# eva01_connectors.net
KiCad netlist of a schematic drawn in Altium Designer
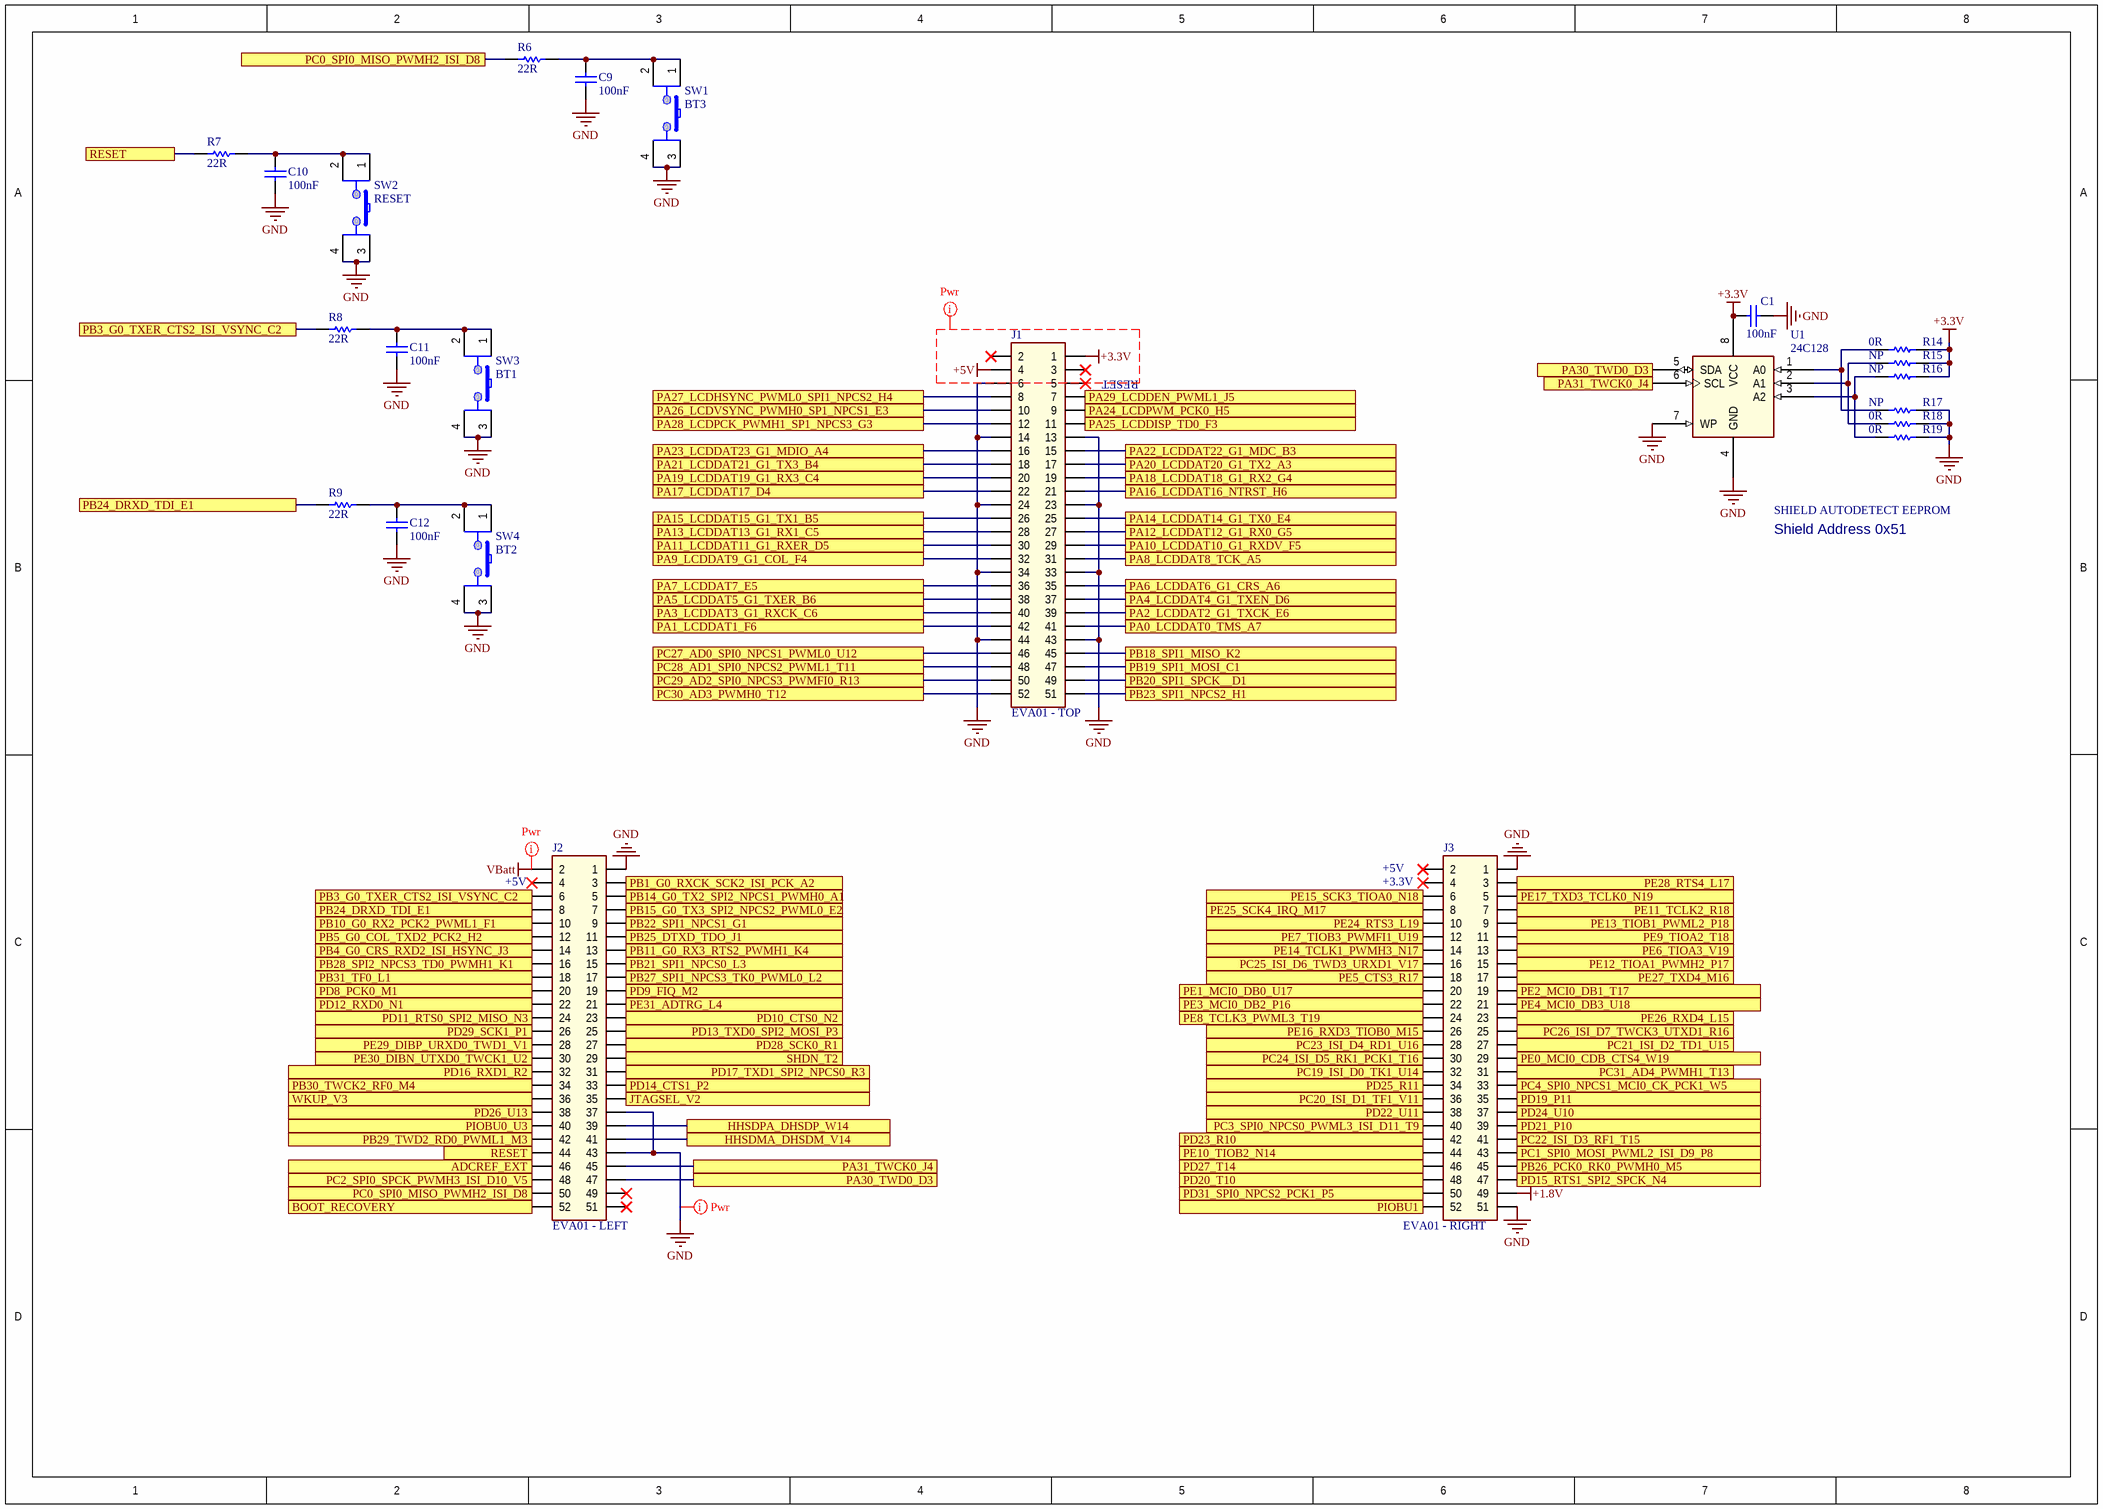
[diagram p0: eva01_connectors.SchDoc]

(export (version "E")
  (design (tool "Eeschema 10.0.6"))
  (components
    (comp (ref "C1")
      (value "100nF")
      (footprint "0603_[1608]")
      (description "Ceramic X7R 50V")
      (fields (field (name "PUBLISHER") "Altium Limited"))
      (libsource (lib "DEVELER_Library") (part "Cap"))
    )
    (comp (ref "C9")
      (value "100nF")
      (footprint "0603_[1608]")
      (description "Ceramic X7R 50V")
      (fields (field (name "PUBLISHER") "Altium Limited"))
      (libsource (lib "DEVELER_Library") (part "Cap"))
    )
    (comp (ref "C10")
      (value "100nF")
      (footprint "0603_[1608]")
      (description "Ceramic X7R 50V")
      (fields (field (name "PUBLISHER") "Altium Limited"))
      (libsource (lib "DEVELER_Library") (part "Cap"))
    )
    (comp (ref "C11")
      (value "100nF")
      (footprint "0603_[1608]")
      (description "Ceramic X7R 50V")
      (fields (field (name "PUBLISHER") "Altium Limited"))
      (libsource (lib "DEVELER_Library") (part "Cap"))
    )
    (comp (ref "C12")
      (value "100nF")
      (footprint "0603_[1608]")
      (description "Ceramic X7R 50V")
      (fields (field (name "PUBLISHER") "Altium Limited"))
      (libsource (lib "DEVELER_Library") (part "Cap"))
    )
    (comp (ref "J1")
      (value "EVA01 - TOP")
      (footprint "SOCKET_2x26_2.54MM_THD")
      (description "Socket Header, 52 pin, 26x2, 2.54mm, H=8.5mm")
      (fields (field (name "PART NUMBER") "Tyco 1-1634688"))
      (libsource (lib "DEVELER_Library") (part "Header 26x2"))
    )
    (comp (ref "J2")
      (value "EVA01 - LEFT")
      (footprint "SOCKET_2x26_2.54MM_THD")
      (description "Socket Header, 52 pin, 26x2, 2.54mm, H=8.5mm")
      (fields (field (name "PART NUMBER") "Tyco 1-1634688"))
      (libsource (lib "DEVELER_Library") (part "Header 26x2"))
    )
    (comp (ref "J3")
      (value "EVA01 - RIGHT")
      (footprint "SOCKET_2x26_2.54MM_THD")
      (description "Socket Header, 52 pin, 26x2, 2.54mm, H=8.5mm")
      (fields (field (name "PART NUMBER") "Tyco 1-1634688"))
      (libsource (lib "DEVELER_Library") (part "Header 26x2"))
    )
    (comp (ref "R6")
      (value "22R")
      (footprint "0603_[1608]")
      (description "Resistor")
      (fields (field (name "PUBLISHER") "Altium Limited"))
      (libsource (lib "DEVELER_Library") (part "Res1"))
    )
    (comp (ref "R7")
      (value "22R")
      (footprint "0603_[1608]")
      (description "Resistor")
      (fields (field (name "PUBLISHER") "Altium Limited"))
      (libsource (lib "DEVELER_Library") (part "Res1"))
    )
    (comp (ref "R8")
      (value "22R")
      (footprint "0603_[1608]")
      (description "Resistor")
      (fields (field (name "PUBLISHER") "Altium Limited"))
      (libsource (lib "DEVELER_Library") (part "Res1"))
    )
    (comp (ref "R9")
      (value "22R")
      (footprint "0603_[1608]")
      (description "Resistor")
      (fields (field (name "PUBLISHER") "Altium Limited"))
      (libsource (lib "DEVELER_Library") (part "Res1"))
    )
    (comp (ref "R14")
      (value "0R")
      (footprint "0603_[1608]")
      (description "Resistor")
      (fields (field (name "PUBLISHER") "Altium Limited"))
      (libsource (lib "project42_lib") (part "Res1"))
    )
    (comp (ref "R15")
      (value "NP")
      (footprint "0603_[1608]")
      (description "Resistor")
      (fields (field (name "PUBLISHER") "Altium Limited"))
      (libsource (lib "project42_lib") (part "Res1"))
    )
    (comp (ref "R16")
      (value "NP")
      (footprint "0603_[1608]")
      (description "Resistor")
      (fields (field (name "PUBLISHER") "Altium Limited"))
      (libsource (lib "project42_lib") (part "Res1"))
    )
    (comp (ref "R17")
      (value "NP")
      (footprint "0603_[1608]")
      (description "Resistor")
      (fields (field (name "PUBLISHER") "Altium Limited"))
      (libsource (lib "project42_lib") (part "Res1"))
    )
    (comp (ref "R18")
      (value "0R")
      (footprint "0603_[1608]")
      (description "Resistor")
      (fields (field (name "PUBLISHER") "Altium Limited"))
      (libsource (lib "project42_lib") (part "Res1"))
    )
    (comp (ref "R19")
      (value "0R")
      (footprint "0603_[1608]")
      (description "Resistor")
      (fields (field (name "PUBLISHER") "Altium Limited"))
      (libsource (lib "project42_lib") (part "Res1"))
    )
    (comp (ref "SW1")
      (value "BT3")
      (footprint "TACTILE_SWITCH_6x6MM_SMD")
      (description "Tactile switch smd H=4.3mm 10x6mm (like cod. Farnell 2435308)")
      (libsource (lib "DEVELER_Library") (part "tactile_switch"))
    )
    (comp (ref "SW2")
      (value "RESET")
      (footprint "TACTILE_SWITCH_6x6MM_SMD")
      (description "Tactile switch smd H=4.3mm 10x6mm (like cod. Farnell 2435308)")
      (libsource (lib "DEVELER_Library") (part "tactile_switch"))
    )
    (comp (ref "SW3")
      (value "BT1")
      (footprint "TACTILE_SWITCH_6x6MM_SMD")
      (description "Tactile switch smd H=4.3mm 10x6mm (like cod. Farnell 2435308)")
      (libsource (lib "DEVELER_Library") (part "tactile_switch"))
    )
    (comp (ref "SW4")
      (value "BT2")
      (footprint "TACTILE_SWITCH_6x6MM_SMD")
      (description "Tactile switch smd H=4.3mm 10x6mm (like cod. Farnell 2435308)")
      (libsource (lib "DEVELER_Library") (part "tactile_switch"))
    )
    (comp (ref "U1")
      (value "24C128")
      (footprint "SOIC8")
      (description "EEPROM")
      (libsource (lib "DEVELER_Library") (part "EEPROM-SOIC8"))
    )
  )
  (nets
    (net (code "1") (name "+1.8V") (class "Default")
      (node (ref "J3") (pin "49") (pinfunction "49_49") (pintype "passive"))
    )
    (net (code "2") (name "+3.3V") (class "Default")
      (node (ref "C1") (pin "2") (pinfunction "2_2") (pintype "passive"))
      (node (ref "J1") (pin "1") (pinfunction "1_1") (pintype "passive"))
      (node (ref "R14") (pin "1") (pinfunction "1_1") (pintype "passive"))
      (node (ref "R15") (pin "1") (pinfunction "1_1") (pintype "passive"))
      (node (ref "R16") (pin "1") (pinfunction "1_1") (pintype "passive"))
      (node (ref "U1") (pin "8") (pinfunction "VCC_8") (pintype "power_in"))
    )
    (net (code "3") (name "+5V") (class "Default")
      (node (ref "J1") (pin "4") (pinfunction "4_4") (pintype "passive"))
    )
    (net (code "4") (name "/ADCREF_EXT") (class "Default")
      (node (ref "J2") (pin "46") (pinfunction "46_46") (pintype "passive"))
    )
    (net (code "5") (name "/BOOT_RECOVERY") (class "Default")
      (node (ref "J2") (pin "52") (pinfunction "52_52") (pintype "passive"))
    )
    (net (code "6") (name "/HHSDMA_DHSDM_V14") (class "Default")
      (node (ref "J2") (pin "41") (pinfunction "41_41") (pintype "passive"))
    )
    (net (code "7") (name "/HHSDPA_DHSDP_W14") (class "Default")
      (node (ref "J2") (pin "39") (pinfunction "39_39") (pintype "passive"))
    )
    (net (code "8") (name "/JTAGSEL_V2") (class "Default")
      (node (ref "J2") (pin "35") (pinfunction "35_35") (pintype "passive"))
    )
    (net (code "9") (name "/PA0_LCDDAT0_TMS_A7") (class "Default")
      (node (ref "J1") (pin "41") (pinfunction "41_41") (pintype "passive"))
    )
    (net (code "10") (name "/PA1_LCDDAT1_F6") (class "Default")
      (node (ref "J1") (pin "42") (pinfunction "42_42") (pintype "passive"))
    )
    (net (code "11") (name "/PA2_LCDDAT2_G1_TXCK_E6") (class "Default")
      (node (ref "J1") (pin "39") (pinfunction "39_39") (pintype "passive"))
    )
    (net (code "12") (name "/PA3_LCDDAT3_G1_RXCK_C6") (class "Default")
      (node (ref "J1") (pin "40") (pinfunction "40_40") (pintype "passive"))
    )
    (net (code "13") (name "/PA4_LCDDAT4_G1_TXEN_D6") (class "Default")
      (node (ref "J1") (pin "37") (pinfunction "37_37") (pintype "passive"))
    )
    (net (code "14") (name "/PA5_LCDDAT5_G1_TXER_B6") (class "Default")
      (node (ref "J1") (pin "38") (pinfunction "38_38") (pintype "passive"))
    )
    (net (code "15") (name "/PA6_LCDDAT6_G1_CRS_A6") (class "Default")
      (node (ref "J1") (pin "35") (pinfunction "35_35") (pintype "passive"))
    )
    (net (code "16") (name "/PA7_LCDDAT7_E5") (class "Default")
      (node (ref "J1") (pin "36") (pinfunction "36_36") (pintype "passive"))
    )
    (net (code "17") (name "/PA8_LCDDAT8_TCK_A5") (class "Default")
      (node (ref "J1") (pin "31") (pinfunction "31_31") (pintype "passive"))
    )
    (net (code "18") (name "/PA9_LCDDAT9_G1_COL_F4") (class "Default")
      (node (ref "J1") (pin "32") (pinfunction "32_32") (pintype "passive"))
    )
    (net (code "19") (name "/PA10_LCDDAT10_G1_RXDV_F5") (class "Default")
      (node (ref "J1") (pin "29") (pinfunction "29_29") (pintype "passive"))
    )
    (net (code "20") (name "/PA11_LCDDAT11_G1_RXER_D5") (class "Default")
      (node (ref "J1") (pin "30") (pinfunction "30_30") (pintype "passive"))
    )
    (net (code "21") (name "/PA12_LCDDAT12_G1_RX0_G5") (class "Default")
      (node (ref "J1") (pin "27") (pinfunction "27_27") (pintype "passive"))
    )
    (net (code "22") (name "/PA13_LCDDAT13_G1_RX1_C5") (class "Default")
      (node (ref "J1") (pin "28") (pinfunction "28_28") (pintype "passive"))
    )
    (net (code "23") (name "/PA14_LCDDAT14_G1_TX0_E4") (class "Default")
      (node (ref "J1") (pin "25") (pinfunction "25_25") (pintype "passive"))
    )
    (net (code "24") (name "/PA15_LCDDAT15_G1_TX1_B5") (class "Default")
      (node (ref "J1") (pin "26") (pinfunction "26_26") (pintype "passive"))
    )
    (net (code "25") (name "/PA16_LCDDAT16_NTRST_H6") (class "Default")
      (node (ref "J1") (pin "21") (pinfunction "21_21") (pintype "passive"))
    )
    (net (code "26") (name "/PA17_LCDDAT17_D4") (class "Default")
      (node (ref "J1") (pin "22") (pinfunction "22_22") (pintype "passive"))
    )
    (net (code "27") (name "/PA18_LCDDAT18_G1_RX2_G4") (class "Default")
      (node (ref "J1") (pin "19") (pinfunction "19_19") (pintype "passive"))
    )
    (net (code "28") (name "/PA19_LCDDAT19_G1_RX3_C4") (class "Default")
      (node (ref "J1") (pin "20") (pinfunction "20_20") (pintype "passive"))
    )
    (net (code "29") (name "/PA20_LCDDAT20_G1_TX2_A3") (class "Default")
      (node (ref "J1") (pin "17") (pinfunction "17_17") (pintype "passive"))
    )
    (net (code "30") (name "/PA21_LCDDAT21_G1_TX3_B4") (class "Default")
      (node (ref "J1") (pin "18") (pinfunction "18_18") (pintype "passive"))
    )
    (net (code "31") (name "/PA22_LCDDAT22_G1_MDC_B3") (class "Default")
      (node (ref "J1") (pin "15") (pinfunction "15_15") (pintype "passive"))
    )
    (net (code "32") (name "/PA23_LCDDAT23_G1_MDIO_A4") (class "Default")
      (node (ref "J1") (pin "16") (pinfunction "16_16") (pintype "passive"))
    )
    (net (code "33") (name "/PA24_LCDPWM_PCK0_H5") (class "Default")
      (node (ref "J1") (pin "9") (pinfunction "9_9") (pintype "passive"))
    )
    (net (code "34") (name "/PA25_LCDDISP_TD0_F3") (class "Default")
      (node (ref "J1") (pin "11") (pinfunction "11_11") (pintype "passive"))
    )
    (net (code "35") (name "/PA26_LCDVSYNC_PWMH0_SP1_NPCS1_E3") (class "Default")
      (node (ref "J1") (pin "10") (pinfunction "10_10") (pintype "passive"))
    )
    (net (code "36") (name "/PA27_LCDHSYNC_PWML0_SPI1_NPCS2_H4") (class "Default")
      (node (ref "J1") (pin "8") (pinfunction "8_8") (pintype "passive"))
    )
    (net (code "37") (name "/PA28_LCDPCK_PWMH1_SP1_NPCS3_G3") (class "Default")
      (node (ref "J1") (pin "12") (pinfunction "12_12") (pintype "passive"))
    )
    (net (code "38") (name "/PA29_LCDDEN_PWML1_J5") (class "Default")
      (node (ref "J1") (pin "7") (pinfunction "7_7") (pintype "passive"))
    )
    (net (code "39") (name "/PA30_TWD0_D3") (class "Default")
      (node (ref "J2") (pin "47") (pinfunction "47_47") (pintype "passive"))
      (node (ref "U1") (pin "5") (pinfunction "SDA_5") (pintype "bidirectional"))
    )
    (net (code "40") (name "/PA31_TWCK0_J4") (class "Default")
      (node (ref "J2") (pin "45") (pinfunction "45_45") (pintype "passive"))
      (node (ref "U1") (pin "6") (pinfunction "SCL_6") (pintype "input"))
    )
    (net (code "41") (name "/PB1_G0_RXCK_SCK2_ISI_PCK_A2") (class "Default")
      (node (ref "J2") (pin "3") (pinfunction "3_3") (pintype "passive"))
    )
    (net (code "42") (name "/PB3_G0_TXER_CTS2_ISI_VSYNC_C2") (class "Default")
      (node (ref "J2") (pin "6") (pinfunction "6_6") (pintype "passive"))
      (node (ref "R8") (pin "2") (pinfunction "2_2") (pintype "passive"))
    )
    (net (code "43") (name "/PB4_G0_CRS_RXD2_ISI_HSYNC_J3") (class "Default")
      (node (ref "J2") (pin "14") (pinfunction "14_14") (pintype "passive"))
    )
    (net (code "44") (name "/PB5_G0_COL_TXD2_PCK2_H2") (class "Default")
      (node (ref "J2") (pin "12") (pinfunction "12_12") (pintype "passive"))
    )
    (net (code "45") (name "/PB10_G0_RX2_PCK2_PWML1_F1") (class "Default")
      (node (ref "J2") (pin "10") (pinfunction "10_10") (pintype "passive"))
    )
    (net (code "46") (name "/PB11_G0_RX3_RTS2_PWMH1_K4") (class "Default")
      (node (ref "J2") (pin "13") (pinfunction "13_13") (pintype "passive"))
    )
    (net (code "47") (name "/PB14_G0_TX2_SPI2_NPCS1_PWMH0_A1") (class "Default")
      (node (ref "J2") (pin "5") (pinfunction "5_5") (pintype "passive"))
    )
    (net (code "48") (name "/PB15_G0_TX3_SPI2_NPCS2_PWML0_E2") (class "Default")
      (node (ref "J2") (pin "7") (pinfunction "7_7") (pintype "passive"))
    )
    (net (code "49") (name "/PB18_SPI1_MISO_K2") (class "Default")
      (node (ref "J1") (pin "45") (pinfunction "45_45") (pintype "passive"))
    )
    (net (code "50") (name "/PB19_SPI1_MOSI_C1") (class "Default")
      (node (ref "J1") (pin "47") (pinfunction "47_47") (pintype "passive"))
    )
    (net (code "51") (name "/PB20_SPI1_SPCK__D1") (class "Default")
      (node (ref "J1") (pin "49") (pinfunction "49_49") (pintype "passive"))
    )
    (net (code "52") (name "/PB21_SPI1_NPCS0_L3") (class "Default")
      (node (ref "J2") (pin "15") (pinfunction "15_15") (pintype "passive"))
    )
    (net (code "53") (name "/PB22_SPI1_NPCS1_G1") (class "Default")
      (node (ref "J2") (pin "9") (pinfunction "9_9") (pintype "passive"))
    )
    (net (code "54") (name "/PB23_SPI1_NPCS2_H1") (class "Default")
      (node (ref "J1") (pin "51") (pinfunction "51_51") (pintype "passive"))
    )
    (net (code "55") (name "/PB24_DRXD_TDI_E1") (class "Default")
      (node (ref "J2") (pin "8") (pinfunction "8_8") (pintype "passive"))
      (node (ref "R9") (pin "2") (pinfunction "2_2") (pintype "passive"))
    )
    (net (code "56") (name "/PB25_DTXD_TDO_J1") (class "Default")
      (node (ref "J2") (pin "11") (pinfunction "11_11") (pintype "passive"))
    )
    (net (code "57") (name "/PB26_PCK0_RK0_PWMH0_M5") (class "Default")
      (node (ref "J3") (pin "45") (pinfunction "45_45") (pintype "passive"))
    )
    (net (code "58") (name "/PB27_SPI1_NPCS3_TK0_PWML0_L2") (class "Default")
      (node (ref "J2") (pin "17") (pinfunction "17_17") (pintype "passive"))
    )
    (net (code "59") (name "/PB28_SPI2_NPCS3_TD0_PWMH1_K1") (class "Default")
      (node (ref "J2") (pin "16") (pinfunction "16_16") (pintype "passive"))
    )
    (net (code "60") (name "/PB29_TWD2_RD0_PWML1_M3") (class "Default")
      (node (ref "J2") (pin "42") (pinfunction "42_42") (pintype "passive"))
    )
    (net (code "61") (name "/PB30_TWCK2_RF0_M4") (class "Default")
      (node (ref "J2") (pin "34") (pinfunction "34_34") (pintype "passive"))
    )
    (net (code "62") (name "/PB31_TF0_L1") (class "Default")
      (node (ref "J2") (pin "18") (pinfunction "18_18") (pintype "passive"))
    )
    (net (code "63") (name "/PC0_SPI0_MISO_PWMH2_ISI_D8") (class "Default")
      (node (ref "J2") (pin "50") (pinfunction "50_50") (pintype "passive"))
      (node (ref "R6") (pin "2") (pinfunction "2_2") (pintype "passive"))
    )
    (net (code "64") (name "/PC1_SPI0_MOSI_PWML2_ISI_D9_P8") (class "Default")
      (node (ref "J3") (pin "43") (pinfunction "43_43") (pintype "passive"))
    )
    (net (code "65") (name "/PC2_SPI0_SPCK_PWMH3_ISI_D10_V5") (class "Default")
      (node (ref "J2") (pin "48") (pinfunction "48_48") (pintype "passive"))
    )
    (net (code "66") (name "/PC3_SPI0_NPCS0_PWML3_ISI_D11_T9") (class "Default")
      (node (ref "J3") (pin "40") (pinfunction "40_40") (pintype "passive"))
    )
    (net (code "67") (name "/PC4_SPI0_NPCS1_MCI0_CK_PCK1_W5") (class "Default")
      (node (ref "J3") (pin "33") (pinfunction "33_33") (pintype "passive"))
    )
    (net (code "68") (name "/PC19_ISI_D0_TK1_U14") (class "Default")
      (node (ref "J3") (pin "32") (pinfunction "32_32") (pintype "passive"))
    )
    (net (code "69") (name "/PC20_ISI_D1_TF1_V11") (class "Default")
      (node (ref "J3") (pin "36") (pinfunction "36_36") (pintype "passive"))
    )
    (net (code "70") (name "/PC21_ISI_D2_TD1_U15") (class "Default")
      (node (ref "J3") (pin "27") (pinfunction "27_27") (pintype "passive"))
    )
    (net (code "71") (name "/PC22_ISI_D3_RF1_T15") (class "Default")
      (node (ref "J3") (pin "41") (pinfunction "41_41") (pintype "passive"))
    )
    (net (code "72") (name "/PC23_ISI_D4_RD1_U16") (class "Default")
      (node (ref "J3") (pin "28") (pinfunction "28_28") (pintype "passive"))
    )
    (net (code "73") (name "/PC24_ISI_D5_RK1_PCK1_T16") (class "Default")
      (node (ref "J3") (pin "30") (pinfunction "30_30") (pintype "passive"))
    )
    (net (code "74") (name "/PC25_ISI_D6_TWD3_URXD1_V17") (class "Default")
      (node (ref "J3") (pin "16") (pinfunction "16_16") (pintype "passive"))
    )
    (net (code "75") (name "/PC26_ISI_D7_TWCK3_UTXD1_R16") (class "Default")
      (node (ref "J3") (pin "25") (pinfunction "25_25") (pintype "passive"))
    )
    (net (code "76") (name "/PC27_AD0_SPI0_NPCS1_PWML0_U12") (class "Default")
      (node (ref "J1") (pin "46") (pinfunction "46_46") (pintype "passive"))
    )
    (net (code "77") (name "/PC28_AD1_SPI0_NPCS2_PWML1_T11") (class "Default")
      (node (ref "J1") (pin "48") (pinfunction "48_48") (pintype "passive"))
    )
    (net (code "78") (name "/PC29_AD2_SPI0_NPCS3_PWMFI0_R13") (class "Default")
      (node (ref "J1") (pin "50") (pinfunction "50_50") (pintype "passive"))
    )
    (net (code "79") (name "/PC30_AD3_PWMH0_T12") (class "Default")
      (node (ref "J1") (pin "52") (pinfunction "52_52") (pintype "passive"))
    )
    (net (code "80") (name "/PC31_AD4_PWMH1_T13") (class "Default")
      (node (ref "J3") (pin "31") (pinfunction "31_31") (pintype "passive"))
    )
    (net (code "81") (name "/PD8_PCK0_M1") (class "Default")
      (node (ref "J2") (pin "20") (pinfunction "20_20") (pintype "passive"))
    )
    (net (code "82") (name "/PD9_FIQ_M2") (class "Default")
      (node (ref "J2") (pin "19") (pinfunction "19_19") (pintype "passive"))
    )
    (net (code "83") (name "/PD10_CTS0_N2") (class "Default")
      (node (ref "J2") (pin "23") (pinfunction "23_23") (pintype "passive"))
    )
    (net (code "84") (name "/PD11_RTS0_SPI2_MISO_N3") (class "Default")
      (node (ref "J2") (pin "24") (pinfunction "24_24") (pintype "passive"))
    )
    (net (code "85") (name "/PD12_RXD0_N1") (class "Default")
      (node (ref "J2") (pin "22") (pinfunction "22_22") (pintype "passive"))
    )
    (net (code "86") (name "/PD13_TXD0_SPI2_MOSI_P3") (class "Default")
      (node (ref "J2") (pin "25") (pinfunction "25_25") (pintype "passive"))
    )
    (net (code "87") (name "/PD14_CTS1_P2") (class "Default")
      (node (ref "J2") (pin "33") (pinfunction "33_33") (pintype "passive"))
    )
    (net (code "88") (name "/PD15_RTS1_SPI2_SPCK_N4") (class "Default")
      (node (ref "J3") (pin "47") (pinfunction "47_47") (pintype "passive"))
    )
    (net (code "89") (name "/PD16_RXD1_R2") (class "Default")
      (node (ref "J2") (pin "32") (pinfunction "32_32") (pintype "passive"))
    )
    (net (code "90") (name "/PD17_TXD1_SPI2_NPCS0_R3") (class "Default")
      (node (ref "J2") (pin "31") (pinfunction "31_31") (pintype "passive"))
    )
    (net (code "91") (name "/PD19_P11") (class "Default")
      (node (ref "J3") (pin "35") (pinfunction "35_35") (pintype "passive"))
    )
    (net (code "92") (name "/PD20_T10") (class "Default")
      (node (ref "J3") (pin "48") (pinfunction "48_48") (pintype "passive"))
    )
    (net (code "93") (name "/PD21_P10") (class "Default")
      (node (ref "J3") (pin "39") (pinfunction "39_39") (pintype "passive"))
    )
    (net (code "94") (name "/PD22_U11") (class "Default")
      (node (ref "J3") (pin "38") (pinfunction "38_38") (pintype "passive"))
    )
    (net (code "95") (name "/PD23_R10") (class "Default")
      (node (ref "J3") (pin "42") (pinfunction "42_42") (pintype "passive"))
    )
    (net (code "96") (name "/PD24_U10") (class "Default")
      (node (ref "J3") (pin "37") (pinfunction "37_37") (pintype "passive"))
    )
    (net (code "97") (name "/PD25_R11") (class "Default")
      (node (ref "J3") (pin "34") (pinfunction "34_34") (pintype "passive"))
    )
    (net (code "98") (name "/PD26_U13") (class "Default")
      (node (ref "J2") (pin "38") (pinfunction "38_38") (pintype "passive"))
    )
    (net (code "99") (name "/PD27_T14") (class "Default")
      (node (ref "J3") (pin "46") (pinfunction "46_46") (pintype "passive"))
    )
    (net (code "100") (name "/PD28_SCK0_R1") (class "Default")
      (node (ref "J2") (pin "27") (pinfunction "27_27") (pintype "passive"))
    )
    (net (code "101") (name "/PD29_SCK1_P1") (class "Default")
      (node (ref "J2") (pin "26") (pinfunction "26_26") (pintype "passive"))
    )
    (net (code "102") (name "/PD31_SPI0_NPCS2_PCK1_P5") (class "Default")
      (node (ref "J3") (pin "50") (pinfunction "50_50") (pintype "passive"))
    )
    (net (code "103") (name "/PE0_MCI0_CDB_CTS4_W19") (class "Default")
      (node (ref "J3") (pin "29") (pinfunction "29_29") (pintype "passive"))
    )
    (net (code "104") (name "/PE1_MCI0_DB0_U17") (class "Default")
      (node (ref "J3") (pin "20") (pinfunction "20_20") (pintype "passive"))
    )
    (net (code "105") (name "/PE2_MCI0_DB1_T17") (class "Default")
      (node (ref "J3") (pin "19") (pinfunction "19_19") (pintype "passive"))
    )
    (net (code "106") (name "/PE3_MCI0_DB2_P16") (class "Default")
      (node (ref "J3") (pin "22") (pinfunction "22_22") (pintype "passive"))
    )
    (net (code "107") (name "/PE4_MCI0_DB3_U18") (class "Default")
      (node (ref "J3") (pin "21") (pinfunction "21_21") (pintype "passive"))
    )
    (net (code "108") (name "/PE5_CTS3_R17") (class "Default")
      (node (ref "J3") (pin "18") (pinfunction "18_18") (pintype "passive"))
    )
    (net (code "109") (name "/PE6_TIOA3_V19") (class "Default")
      (node (ref "J3") (pin "13") (pinfunction "13_13") (pintype "passive"))
    )
    (net (code "110") (name "/PE7_TIOB3_PWMFI1_U19") (class "Default")
      (node (ref "J3") (pin "12") (pinfunction "12_12") (pintype "passive"))
    )
    (net (code "111") (name "/PE8_TCLK3_PWML3_T19") (class "Default")
      (node (ref "J3") (pin "24") (pinfunction "24_24") (pintype "passive"))
    )
    (net (code "112") (name "/PE9_TIOA2_T18") (class "Default")
      (node (ref "J3") (pin "11") (pinfunction "11_11") (pintype "passive"))
    )
    (net (code "113") (name "/PE10_TIOB2_N14") (class "Default")
      (node (ref "J3") (pin "44") (pinfunction "44_44") (pintype "passive"))
    )
    (net (code "114") (name "/PE11_TCLK2_R18") (class "Default")
      (node (ref "J3") (pin "7") (pinfunction "7_7") (pintype "passive"))
    )
    (net (code "115") (name "/PE12_TIOA1_PWMH2_P17") (class "Default")
      (node (ref "J3") (pin "15") (pinfunction "15_15") (pintype "passive"))
    )
    (net (code "116") (name "/PE13_TIOB1_PWML2_P18") (class "Default")
      (node (ref "J3") (pin "9") (pinfunction "9_9") (pintype "passive"))
    )
    (net (code "117") (name "/PE14_TCLK1_PWMH3_N17") (class "Default")
      (node (ref "J3") (pin "14") (pinfunction "14_14") (pintype "passive"))
    )
    (net (code "118") (name "/PE15_SCK3_TIOA0_N18") (class "Default")
      (node (ref "J3") (pin "6") (pinfunction "6_6") (pintype "passive"))
    )
    (net (code "119") (name "/PE16_RXD3_TIOB0_M15") (class "Default")
      (node (ref "J3") (pin "26") (pinfunction "26_26") (pintype "passive"))
    )
    (net (code "120") (name "/PE17_TXD3_TCLK0_N19") (class "Default")
      (node (ref "J3") (pin "5") (pinfunction "5_5") (pintype "passive"))
    )
    (net (code "121") (name "/PE24_RTS3_L19") (class "Default")
      (node (ref "J3") (pin "10") (pinfunction "10_10") (pintype "passive"))
    )
    (net (code "122") (name "/PE25_SCK4_IRQ_M17") (class "Default")
      (node (ref "J3") (pin "8") (pinfunction "8_8") (pintype "passive"))
    )
    (net (code "123") (name "/PE26_RXD4_L15") (class "Default")
      (node (ref "J3") (pin "23") (pinfunction "23_23") (pintype "passive"))
    )
    (net (code "124") (name "/PE27_TXD4_M16") (class "Default")
      (node (ref "J3") (pin "17") (pinfunction "17_17") (pintype "passive"))
    )
    (net (code "125") (name "/PE28_RTS4_L17") (class "Default")
      (node (ref "J3") (pin "3") (pinfunction "3_3") (pintype "passive"))
    )
    (net (code "126") (name "/PE29_DIBP_URXD0_TWD1_V1") (class "Default")
      (node (ref "J2") (pin "28") (pinfunction "28_28") (pintype "passive"))
    )
    (net (code "127") (name "/PE30_DIBN_UTXD0_TWCK1_U2") (class "Default")
      (node (ref "J2") (pin "30") (pinfunction "30_30") (pintype "passive"))
    )
    (net (code "128") (name "/PE31_ADTRG_L4") (class "Default")
      (node (ref "J2") (pin "21") (pinfunction "21_21") (pintype "passive"))
    )
    (net (code "129") (name "/PIOBU0_U3") (class "Default")
      (node (ref "J2") (pin "40") (pinfunction "40_40") (pintype "passive"))
    )
    (net (code "130") (name "/PIOBU1") (class "Default")
      (node (ref "J3") (pin "52") (pinfunction "52_52") (pintype "passive"))
    )
    (net (code "131") (name "/RESET") (class "Default")
      (node (ref "J2") (pin "44") (pinfunction "44_44") (pintype "passive"))
      (node (ref "R7") (pin "2") (pinfunction "2_2") (pintype "passive"))
    )
    (net (code "132") (name "/SHDN_T2") (class "Default")
      (node (ref "J2") (pin "29") (pinfunction "29_29") (pintype "passive"))
    )
    (net (code "133") (name "/WKUP_V3") (class "Default")
      (node (ref "J2") (pin "36") (pinfunction "36_36") (pintype "passive"))
    )
    (net (code "134") (name "GND") (class "Default")
      (node (ref "C1") (pin "1") (pinfunction "1_1") (pintype "passive"))
      (node (ref "C10") (pin "1") (pinfunction "1_1") (pintype "passive"))
      (node (ref "C11") (pin "1") (pinfunction "1_1") (pintype "passive"))
      (node (ref "C12") (pin "1") (pinfunction "1_1") (pintype "passive"))
      (node (ref "C9") (pin "1") (pinfunction "1_1") (pintype "passive"))
      (node (ref "J1") (pin "13") (pinfunction "13_13") (pintype "passive"))
      (node (ref "J1") (pin "14") (pinfunction "14_14") (pintype "passive"))
      (node (ref "J1") (pin "23") (pinfunction "23_23") (pintype "passive"))
      (node (ref "J1") (pin "24") (pinfunction "24_24") (pintype "passive"))
      (node (ref "J1") (pin "33") (pinfunction "33_33") (pintype "passive"))
      (node (ref "J1") (pin "34") (pinfunction "34_34") (pintype "passive"))
      (node (ref "J1") (pin "43") (pinfunction "43_43") (pintype "passive"))
      (node (ref "J1") (pin "44") (pinfunction "44_44") (pintype "passive"))
      (node (ref "J1") (pin "6") (pinfunction "6_6") (pintype "passive"))
      (node (ref "J2") (pin "1") (pinfunction "1_1") (pintype "passive"))
      (node (ref "J2") (pin "37") (pinfunction "37_37") (pintype "passive"))
      (node (ref "J2") (pin "43") (pinfunction "43_43") (pintype "passive"))
      (node (ref "J3") (pin "1") (pinfunction "1_1") (pintype "passive"))
      (node (ref "J3") (pin "51") (pinfunction "51_51") (pintype "passive"))
      (node (ref "R17") (pin "1") (pinfunction "1_1") (pintype "passive"))
      (node (ref "R18") (pin "1") (pinfunction "1_1") (pintype "passive"))
      (node (ref "R19") (pin "1") (pinfunction "1_1") (pintype "passive"))
      (node (ref "SW1") (pin "3") (pinfunction "3_3") (pintype "passive"))
      (node (ref "SW1") (pin "4") (pinfunction "4_4") (pintype "passive"))
      (node (ref "SW2") (pin "3") (pinfunction "3_3") (pintype "passive"))
      (node (ref "SW2") (pin "4") (pinfunction "4_4") (pintype "passive"))
      (node (ref "SW3") (pin "3") (pinfunction "3_3") (pintype "passive"))
      (node (ref "SW3") (pin "4") (pinfunction "4_4") (pintype "passive"))
      (node (ref "SW4") (pin "3") (pinfunction "3_3") (pintype "passive"))
      (node (ref "SW4") (pin "4") (pinfunction "4_4") (pintype "passive"))
      (node (ref "U1") (pin "4") (pinfunction "GND_4") (pintype "power_in"))
      (node (ref "U1") (pin "7") (pinfunction "WP_7") (pintype "input"))
    )
    (net (code "135") (name "Net-(C9-Pad2)") (class "Default")
      (node (ref "C9") (pin "2") (pinfunction "2_2") (pintype "passive"))
      (node (ref "R6") (pin "1") (pinfunction "1_1") (pintype "passive"))
      (node (ref "SW1") (pin "1") (pinfunction "1_1") (pintype "passive"))
      (node (ref "SW1") (pin "2") (pinfunction "2_2") (pintype "passive"))
    )
    (net (code "136") (name "Net-(C10-Pad2)") (class "Default")
      (node (ref "C10") (pin "2") (pinfunction "2_2") (pintype "passive"))
      (node (ref "R7") (pin "1") (pinfunction "1_1") (pintype "passive"))
      (node (ref "SW2") (pin "1") (pinfunction "1_1") (pintype "passive"))
      (node (ref "SW2") (pin "2") (pinfunction "2_2") (pintype "passive"))
    )
    (net (code "137") (name "Net-(C11-Pad2)") (class "Default")
      (node (ref "C11") (pin "2") (pinfunction "2_2") (pintype "passive"))
      (node (ref "R8") (pin "1") (pinfunction "1_1") (pintype "passive"))
      (node (ref "SW3") (pin "1") (pinfunction "1_1") (pintype "passive"))
      (node (ref "SW3") (pin "2") (pinfunction "2_2") (pintype "passive"))
    )
    (net (code "138") (name "Net-(C12-Pad2)") (class "Default")
      (node (ref "C12") (pin "2") (pinfunction "2_2") (pintype "passive"))
      (node (ref "R9") (pin "1") (pinfunction "1_1") (pintype "passive"))
      (node (ref "SW4") (pin "1") (pinfunction "1_1") (pintype "passive"))
      (node (ref "SW4") (pin "2") (pinfunction "2_2") (pintype "passive"))
    )
    (net (code "139") (name "Net-(U1-A0)") (class "Default")
      (node (ref "R14") (pin "2") (pinfunction "2_2") (pintype "passive"))
      (node (ref "R17") (pin "2") (pinfunction "2_2") (pintype "passive"))
      (node (ref "U1") (pin "1") (pinfunction "A0_1") (pintype "input"))
    )
    (net (code "140") (name "Net-(U1-A1)") (class "Default")
      (node (ref "R15") (pin "2") (pinfunction "2_2") (pintype "passive"))
      (node (ref "R18") (pin "2") (pinfunction "2_2") (pintype "passive"))
      (node (ref "U1") (pin "2") (pinfunction "A1_2") (pintype "input"))
    )
    (net (code "141") (name "Net-(U1-A2)") (class "Default")
      (node (ref "R16") (pin "2") (pinfunction "2_2") (pintype "passive"))
      (node (ref "R19") (pin "2") (pinfunction "2_2") (pintype "passive"))
      (node (ref "U1") (pin "3") (pinfunction "A2_3") (pintype "input"))
    )
    (net (code "142") (name "VBatt") (class "Default")
      (node (ref "J2") (pin "2") (pinfunction "2_2") (pintype "passive"))
    )
    (net (code "143") (name "unconnected-(J1-Pad2)") (class "Default")
      (node (ref "J1") (pin "2") (pinfunction "2_2") (pintype "passive+no_connect"))
    )
    (net (code "144") (name "unconnected-(J1-Pad3)") (class "Default")
      (node (ref "J1") (pin "3") (pinfunction "3_3") (pintype "passive+no_connect"))
    )
    (net (code "145") (name "unconnected-(J1-Pad5)") (class "Default")
      (node (ref "J1") (pin "5") (pinfunction "5_5") (pintype "passive+no_connect"))
    )
    (net (code "146") (name "unconnected-(J2-Pad4)") (class "Default")
      (node (ref "J2") (pin "4") (pinfunction "4_4") (pintype "passive+no_connect"))
    )
    (net (code "147") (name "unconnected-(J2-Pad49)") (class "Default")
      (node (ref "J2") (pin "49") (pinfunction "49_49") (pintype "passive+no_connect"))
    )
    (net (code "148") (name "unconnected-(J2-Pad51)") (class "Default")
      (node (ref "J2") (pin "51") (pinfunction "51_51") (pintype "passive+no_connect"))
    )
    (net (code "149") (name "unconnected-(J3-Pad2)") (class "Default")
      (node (ref "J3") (pin "2") (pinfunction "2_2") (pintype "passive+no_connect"))
    )
    (net (code "150") (name "unconnected-(J3-Pad4)") (class "Default")
      (node (ref "J3") (pin "4") (pinfunction "4_4") (pintype "passive+no_connect"))
    )
  )
)
